# LB_BIT_w21_SUM-v03_1_0x.net
KiCad netlist of a schematic drawn in EAGLE
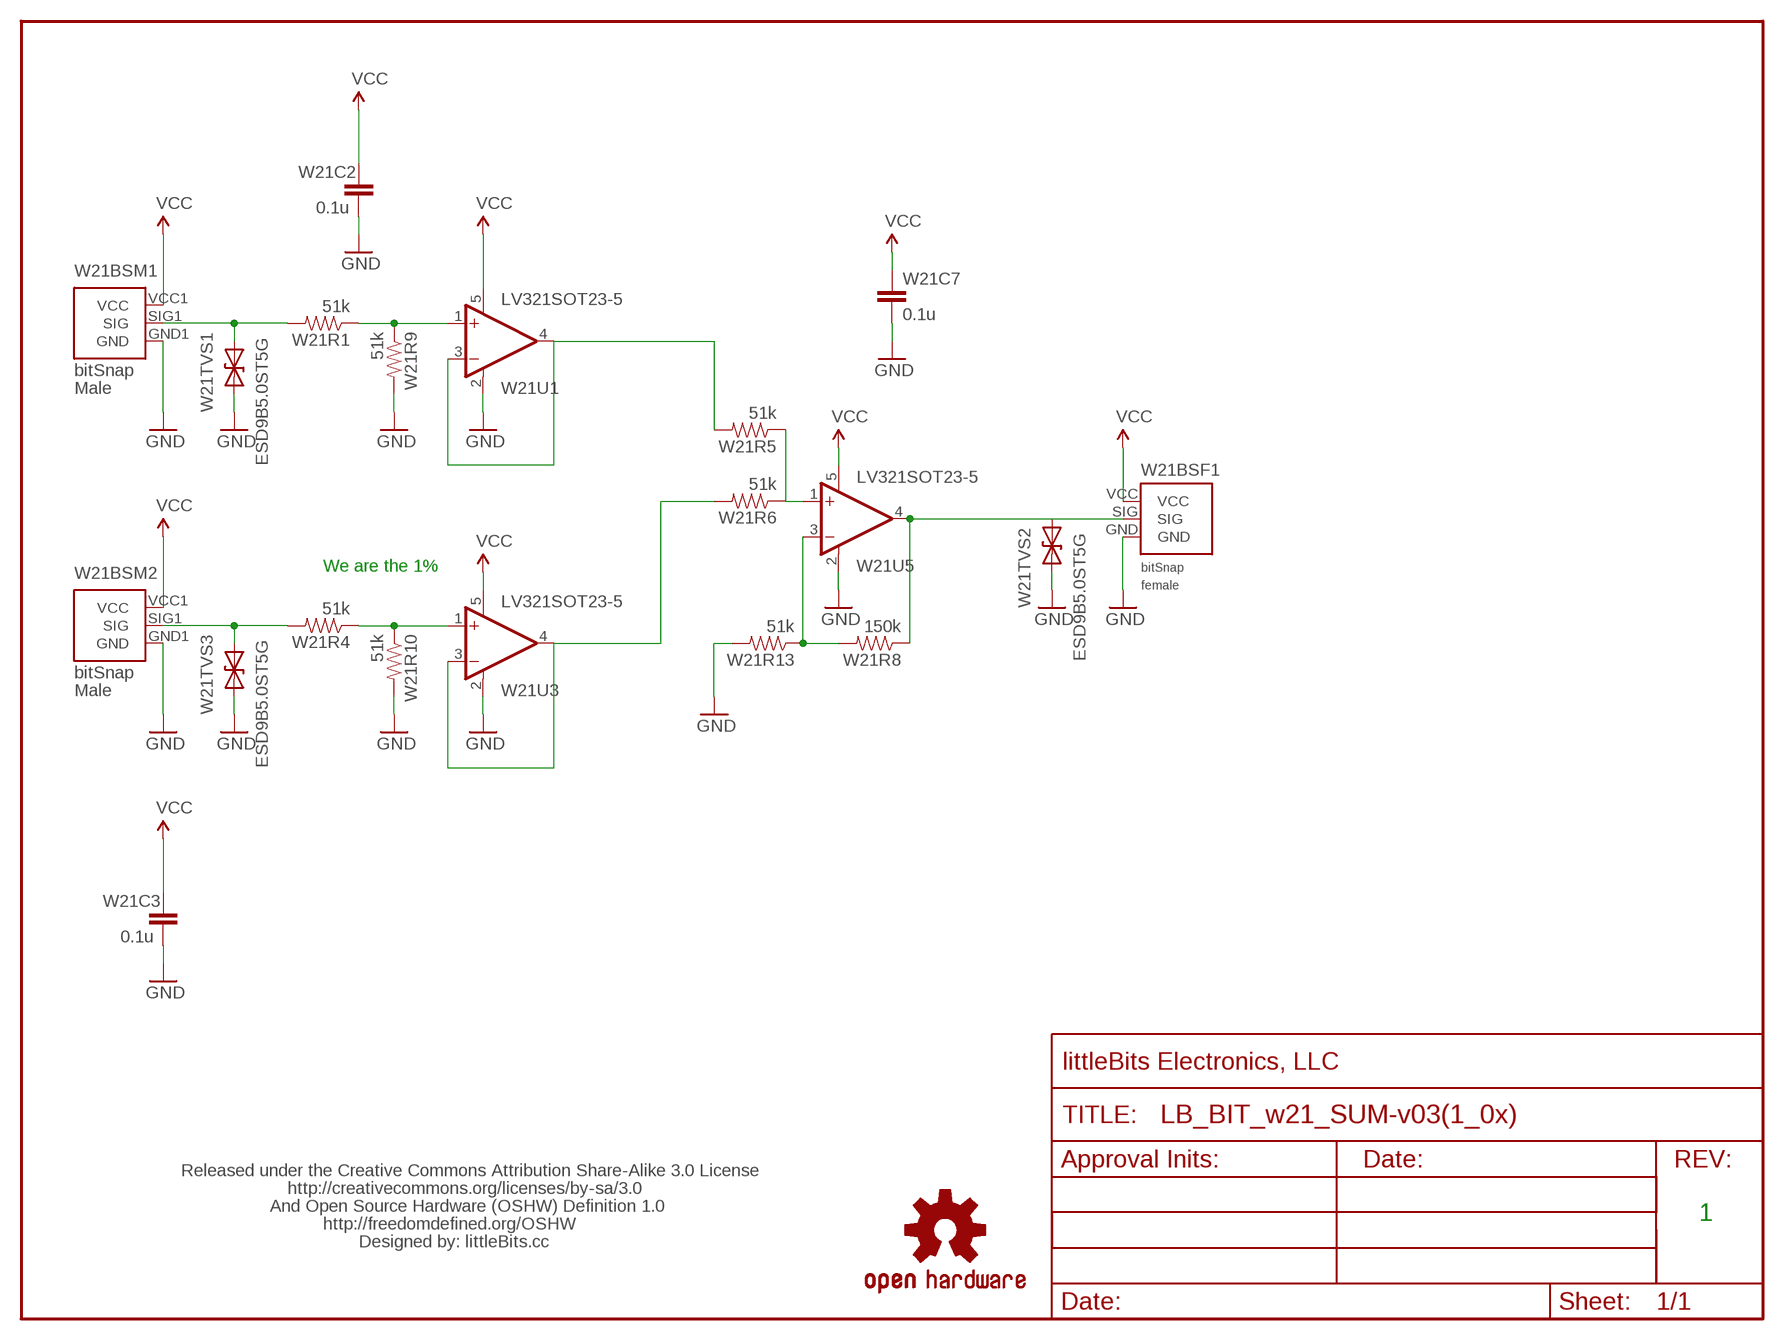
[diagram p0: schematic, sheet 1]

(export (version "E")
  (design (tool "Eeschema 10.0.6"))
  (components
    (comp (ref "FRAME1")
      (value "FRAME-LETTER")
      (footprint "eagle-import:FABDWG01")
      (libsource (lib "eagle-import") (part "FRAME-LETTER"))
    )
    (comp (ref "U$1")
      (value "OSHWCREDIT")
      (footprint "eagle-import:OSHWCREDIT")
      (libsource (lib "eagle-import") (part "OSHWCREDIT"))
    )
    (comp (ref "U$2")
      (value "OSHW-LOGOL")
      (footprint "eagle-import:OSHW-LOGO-L")
      (libsource (lib "eagle-import") (part "OSHW-LOGOL"))
    )
    (comp (ref "W21BSF1")
      (value "BITSNAP_V03_FEMALE")
      (footprint "eagle-import:BITSNAP_V03_FEMALE")
      (libsource (lib "eagle-import") (part "BITSNAP_V03_FEMALE"))
    )
    (comp (ref "W21BSM1")
      (value "BITSNAP_V03_MALE")
      (footprint "eagle-import:BITSNAP_V03_MALE")
      (libsource (lib "eagle-import") (part "BITSNAP_V03_MALE"))
    )
    (comp (ref "W21BSM2")
      (value "BITSNAP_V03_MALE")
      (footprint "eagle-import:BITSNAP_V03_MALE")
      (libsource (lib "eagle-import") (part "BITSNAP_V03_MALE"))
    )
    (comp (ref "W21C2")
      (value "0.1u")
      (footprint "eagle-import:CAP-0603")
      (libsource (lib "eagle-import") (part "CAPCAP-0603"))
    )
    (comp (ref "W21C3")
      (value "0.1u")
      (footprint "eagle-import:CAP-0603")
      (libsource (lib "eagle-import") (part "CAPCAP-0603"))
    )
    (comp (ref "W21C7")
      (value "0.1u")
      (footprint "eagle-import:CAP-0603")
      (libsource (lib "eagle-import") (part "CAPCAP-0603"))
    )
    (comp (ref "W21R1")
      (value "51k")
      (footprint "eagle-import:RES-0603")
      (libsource (lib "eagle-import") (part "RESISTOR0603"))
    )
    (comp (ref "W21R4")
      (value "51k")
      (footprint "eagle-import:RES-0603")
      (libsource (lib "eagle-import") (part "RESISTOR0603"))
    )
    (comp (ref "W21R5")
      (value "51k")
      (footprint "eagle-import:RES-0603")
      (libsource (lib "eagle-import") (part "RESISTOR0603"))
    )
    (comp (ref "W21R6")
      (value "51k")
      (footprint "eagle-import:RES-0603")
      (libsource (lib "eagle-import") (part "RESISTOR0603"))
    )
    (comp (ref "W21R8")
      (value "150k")
      (footprint "eagle-import:RES-0603")
      (libsource (lib "eagle-import") (part "RESISTOR0603"))
    )
    (comp (ref "W21R9")
      (value "51k")
      (footprint "eagle-import:RES-0603")
      (libsource (lib "eagle-import") (part "RESISTOR0603"))
    )
    (comp (ref "W21R10")
      (value "51k")
      (footprint "eagle-import:RES-0603")
      (libsource (lib "eagle-import") (part "RESISTOR0603"))
    )
    (comp (ref "W21R13")
      (value "51k")
      (footprint "eagle-import:RES-0603")
      (libsource (lib "eagle-import") (part "RESISTOR0603"))
    )
    (comp (ref "W21TVS1")
      (value "ESD9B5.0ST5G")
      (footprint "eagle-import:SOD-923")
      (libsource (lib "eagle-import") (part "DIODE-TVSSOD-923"))
    )
    (comp (ref "W21TVS2")
      (value "ESD9B5.0ST5G")
      (footprint "eagle-import:SOD-923")
      (libsource (lib "eagle-import") (part "DIODE-TVSSOD-923"))
    )
    (comp (ref "W21TVS3")
      (value "ESD9B5.0ST5G")
      (footprint "eagle-import:SOD-923")
      (libsource (lib "eagle-import") (part "DIODE-TVSSOD-923"))
    )
    (comp (ref "W21U1")
      (value "LV321SOT23-5")
      (footprint "eagle-import:SOT23-5")
      (libsource (lib "eagle-import") (part "LV321SOT23-5"))
    )
    (comp (ref "W21U3")
      (value "LV321SOT23-5")
      (footprint "eagle-import:SOT23-5")
      (libsource (lib "eagle-import") (part "LV321SOT23-5"))
    )
    (comp (ref "W21U5")
      (value "LV321SOT23-5")
      (footprint "eagle-import:SOT23-5")
      (libsource (lib "eagle-import") (part "LV321SOT23-5"))
    )
  )
  (nets
    (net (code "1") (name "GND") (class "Default")
      (node (ref "W21BSF1") (pin "GND") (pinfunction "GND_GND") (pintype "bidirectional"))
      (node (ref "W21BSM1") (pin "GND1") (pinfunction "GND_GND1") (pintype "bidirectional"))
      (node (ref "W21BSM2") (pin "GND1") (pinfunction "GND_GND1") (pintype "bidirectional"))
      (node (ref "W21C2") (pin "2") (pinfunction "2_2") (pintype "passive"))
      (node (ref "W21C3") (pin "2") (pinfunction "2_2") (pintype "passive"))
      (node (ref "W21C7") (pin "2") (pinfunction "2_2") (pintype "passive"))
      (node (ref "W21R10") (pin "2") (pinfunction "2_2") (pintype "passive"))
      (node (ref "W21R13") (pin "2") (pinfunction "2_2") (pintype "passive"))
      (node (ref "W21R9") (pin "2") (pinfunction "2_2") (pintype "passive"))
      (node (ref "W21TVS1") (pin "1") (pinfunction "A_1") (pintype "passive"))
      (node (ref "W21TVS2") (pin "1") (pinfunction "A_1") (pintype "passive"))
      (node (ref "W21TVS3") (pin "1") (pinfunction "A_1") (pintype "passive"))
      (node (ref "W21U1") (pin "2") (pinfunction "V-_2") (pintype "power_in"))
      (node (ref "W21U3") (pin "2") (pinfunction "V-_2") (pintype "power_in"))
      (node (ref "W21U5") (pin "2") (pinfunction "V-_2") (pintype "power_in"))
    )
    (net (code "2") (name "Net-(W21BSM1-SIG)") (class "Default")
      (node (ref "W21BSM1") (pin "SIG1") (pinfunction "SIG_SIG1") (pintype "bidirectional"))
      (node (ref "W21R1") (pin "2") (pinfunction "2_2") (pintype "passive"))
      (node (ref "W21TVS1") (pin "2") (pinfunction "C_2") (pintype "passive"))
    )
    (net (code "3") (name "Net-(W21BSM2-SIG)") (class "Default")
      (node (ref "W21BSM2") (pin "SIG1") (pinfunction "SIG_SIG1") (pintype "bidirectional"))
      (node (ref "W21R4") (pin "2") (pinfunction "2_2") (pintype "passive"))
      (node (ref "W21TVS3") (pin "2") (pinfunction "C_2") (pintype "passive"))
    )
    (net (code "4") (name "Net-(W21TVS2-C)") (class "Default")
      (node (ref "W21BSF1") (pin "SIG") (pinfunction "SIG_SIG") (pintype "bidirectional"))
      (node (ref "W21R8") (pin "1") (pinfunction "1_1") (pintype "passive"))
      (node (ref "W21TVS2") (pin "2") (pinfunction "C_2") (pintype "passive"))
      (node (ref "W21U5") (pin "4") (pinfunction "OUT_4") (pintype "output"))
    )
    (net (code "5") (name "Net-(W21U1-+IN)") (class "Default")
      (node (ref "W21R1") (pin "1") (pinfunction "1_1") (pintype "passive"))
      (node (ref "W21R9") (pin "1") (pinfunction "1_1") (pintype "passive"))
      (node (ref "W21U1") (pin "1") (pinfunction "+IN_1") (pintype "input"))
    )
    (net (code "6") (name "Net-(W21U1--IN)") (class "Default")
      (node (ref "W21R5") (pin "2") (pinfunction "2_2") (pintype "passive"))
      (node (ref "W21U1") (pin "3") (pinfunction "-IN_3") (pintype "input"))
      (node (ref "W21U1") (pin "4") (pinfunction "OUT_4") (pintype "output"))
    )
    (net (code "7") (name "Net-(W21U3-+IN)") (class "Default")
      (node (ref "W21R10") (pin "1") (pinfunction "1_1") (pintype "passive"))
      (node (ref "W21R4") (pin "1") (pinfunction "1_1") (pintype "passive"))
      (node (ref "W21U3") (pin "1") (pinfunction "+IN_1") (pintype "input"))
    )
    (net (code "8") (name "Net-(W21U3--IN)") (class "Default")
      (node (ref "W21R6") (pin "2") (pinfunction "2_2") (pintype "passive"))
      (node (ref "W21U3") (pin "3") (pinfunction "-IN_3") (pintype "input"))
      (node (ref "W21U3") (pin "4") (pinfunction "OUT_4") (pintype "output"))
    )
    (net (code "9") (name "Net-(W21U5-+IN)") (class "Default")
      (node (ref "W21R5") (pin "1") (pinfunction "1_1") (pintype "passive"))
      (node (ref "W21R6") (pin "1") (pinfunction "1_1") (pintype "passive"))
      (node (ref "W21U5") (pin "1") (pinfunction "+IN_1") (pintype "input"))
    )
    (net (code "10") (name "Net-(W21U5--IN)") (class "Default")
      (node (ref "W21R13") (pin "1") (pinfunction "1_1") (pintype "passive"))
      (node (ref "W21R8") (pin "2") (pinfunction "2_2") (pintype "passive"))
      (node (ref "W21U5") (pin "3") (pinfunction "-IN_3") (pintype "input"))
    )
    (net (code "11") (name "VCC") (class "Default")
      (node (ref "W21BSF1") (pin "VCC") (pinfunction "VCC_VCC") (pintype "bidirectional"))
      (node (ref "W21BSM1") (pin "VCC1") (pinfunction "VCC_VCC1") (pintype "bidirectional"))
      (node (ref "W21BSM2") (pin "VCC1") (pinfunction "VCC_VCC1") (pintype "bidirectional"))
      (node (ref "W21C2") (pin "1") (pinfunction "1_1") (pintype "passive"))
      (node (ref "W21C3") (pin "1") (pinfunction "1_1") (pintype "passive"))
      (node (ref "W21C7") (pin "1") (pinfunction "1_1") (pintype "passive"))
      (node (ref "W21U1") (pin "5") (pinfunction "V+_5") (pintype "power_in"))
      (node (ref "W21U3") (pin "5") (pinfunction "V+_5") (pintype "power_in"))
      (node (ref "W21U5") (pin "5") (pinfunction "V+_5") (pintype "power_in"))
    )
  )
)
